# SCHEMATIC_e_BOOK_READER__VERSIUNE_10_v26.net
KiCad netlist of a schematic drawn in EAGLE
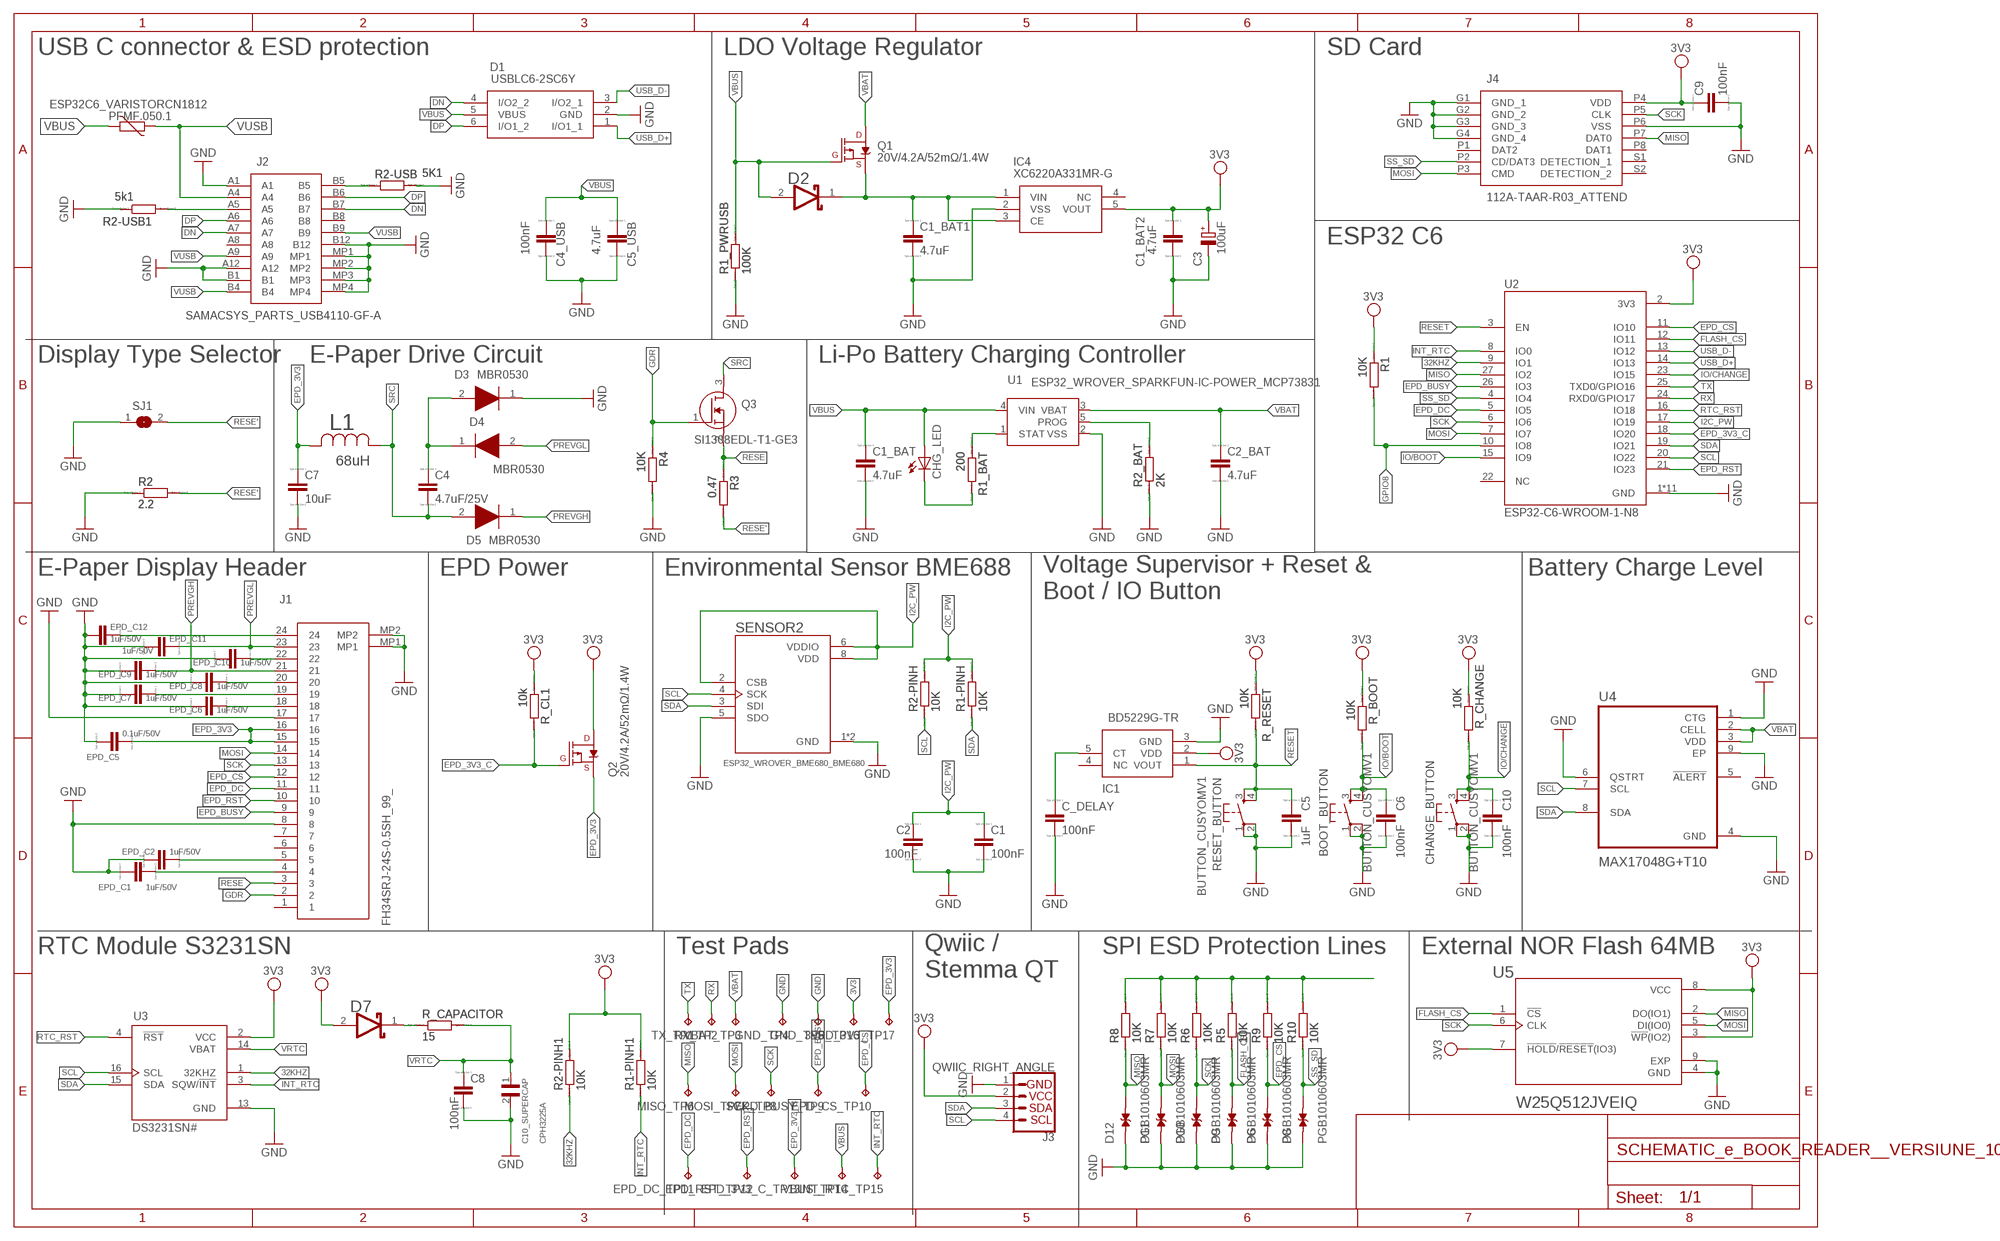
[diagram p0: schematic, sheet 1]

(export (version "E")
  (design (tool "Eeschema 10.0.6"))
  (components
    (comp (ref "3V3_TP16")
      (value "TPTP20R")
      (footprint "eagle-import:TP20R")
      (libsource (lib "eagle-import") (part "TPTP20R"))
    )
    (comp (ref "BOOT_BUTTON")
      (value "BUTTON_CUSYOMV1")
      (footprint "eagle-import:MYBUTTON")
      (libsource (lib "eagle-import") (part "BUTTON_CUSYOMV1"))
    )
    (comp (ref "C1")
      (value "100nF")
      (footprint "eagle-import:ESP32_WROVER_EAGLE-LTSPICE_C0402")
      (libsource (lib "eagle-import") (part "ESP32_WROVER_EAGLE-LTSPICE_CC0402"))
    )
    (comp (ref "C1_BAT")
      (value "4.7uF")
      (footprint "eagle-import:ESP32_WROVER_EAGLE-LTSPICE_C0402")
      (libsource (lib "eagle-import") (part "ESP32_WROVER_EAGLE-LTSPICE_CC0402"))
    )
    (comp (ref "C1_BAT1")
      (value "4.7uF")
      (footprint "eagle-import:ESP32_WROVER_EAGLE-LTSPICE_C0402")
      (libsource (lib "eagle-import") (part "ESP32_WROVER_EAGLE-LTSPICE_CC0402"))
    )
    (comp (ref "C1_BAT2")
      (value "4.7uF")
      (footprint "eagle-import:ESP32_WROVER_EAGLE-LTSPICE_C0402")
      (libsource (lib "eagle-import") (part "ESP32_WROVER_EAGLE-LTSPICE_CC0402"))
    )
    (comp (ref "C2")
      (value "100nF")
      (footprint "eagle-import:ESP32_WROVER_EAGLE-LTSPICE_C0402")
      (libsource (lib "eagle-import") (part "ESP32_WROVER_EAGLE-LTSPICE_CC0402"))
    )
    (comp (ref "C2_BAT")
      (value "4.7uF")
      (footprint "eagle-import:ESP32_WROVER_EAGLE-LTSPICE_C0402")
      (libsource (lib "eagle-import") (part "ESP32_WROVER_EAGLE-LTSPICE_CC0402"))
    )
    (comp (ref "C3")
      (value "100uF")
      (footprint "eagle-import:RCL_CT3528")
      (libsource (lib "eagle-import") (part "RCL_CPOL-EUCT3528"))
    )
    (comp (ref "C4")
      (value "4.7uF/25V")
      (footprint "eagle-import:ESP32_WROVER_EAGLE-LTSPICE_C0402")
      (libsource (lib "eagle-import") (part "ESP32_WROVER_EAGLE-LTSPICE_CC0402"))
    )
    (comp (ref "C4_USB")
      (value "100nF")
      (footprint "eagle-import:ESP32_WROVER_EAGLE-LTSPICE_C0402")
      (libsource (lib "eagle-import") (part "ESP32_WROVER_EAGLE-LTSPICE_CC0402"))
    )
    (comp (ref "C5")
      (value "1uF")
      (footprint "eagle-import:ESP32_WROVER_EAGLE-LTSPICE_C0402")
      (libsource (lib "eagle-import") (part "ESP32_WROVER_EAGLE-LTSPICE_CC0402"))
    )
    (comp (ref "C5_USB")
      (value "4.7uF")
      (footprint "eagle-import:ESP32_WROVER_EAGLE-LTSPICE_C0402")
      (libsource (lib "eagle-import") (part "ESP32_WROVER_EAGLE-LTSPICE_CC0402"))
    )
    (comp (ref "C6")
      (value "100nF")
      (footprint "eagle-import:ESP32_WROVER_EAGLE-LTSPICE_C0402")
      (libsource (lib "eagle-import") (part "ESP32_WROVER_EAGLE-LTSPICE_CC0402"))
    )
    (comp (ref "C7")
      (value "10uF")
      (footprint "eagle-import:ESP32_WROVER_EAGLE-LTSPICE_C0402")
      (libsource (lib "eagle-import") (part "ESP32_WROVER_EAGLE-LTSPICE_CC0402"))
    )
    (comp (ref "C8")
      (value "100nF")
      (footprint "eagle-import:ESP32_WROVER_EAGLE-LTSPICE_C0402")
      (libsource (lib "eagle-import") (part "ESP32_WROVER_EAGLE-LTSPICE_CC0402"))
    )
    (comp (ref "C9")
      (value "100nF")
      (footprint "eagle-import:ESP32_WROVER_EAGLE-LTSPICE_C0402")
      (libsource (lib "eagle-import") (part "ESP32_WROVER_EAGLE-LTSPICE_CC0402"))
    )
    (comp (ref "C10")
      (value "100nF")
      (footprint "eagle-import:ESP32_WROVER_EAGLE-LTSPICE_C0402")
      (libsource (lib "eagle-import") (part "ESP32_WROVER_EAGLE-LTSPICE_CC0402"))
    )
    (comp (ref "C10_SUPERCAP")
      (value "CPH3225A")
      (footprint "eagle-import:CAPCP3225X100N")
      (fields (field (name "MF") "Seiko Instruments"))
      (libsource (lib "eagle-import") (part "CPH3225A"))
    )
    (comp (ref "CHANGE_BUTTON")
      (value "BUTTON_CUSYOMV1")
      (footprint "eagle-import:MYBUTTON")
      (libsource (lib "eagle-import") (part "BUTTON_CUSYOMV1"))
    )
    (comp (ref "CHG_LED")
      (value "ADAFRUIT_LEDCHIP-LED0603")
      (footprint "eagle-import:ADAFRUIT_CHIP-LED0603")
      (libsource (lib "eagle-import") (part "ADAFRUIT_LEDCHIP-LED0603"))
    )
    (comp (ref "C_DELAY")
      (value "100nF")
      (footprint "eagle-import:ESP32_WROVER_EAGLE-LTSPICE_C0402")
      (libsource (lib "eagle-import") (part "ESP32_WROVER_EAGLE-LTSPICE_CC0402"))
    )
    (comp (ref "D1")
      (value "USBLC6-2SC6Y")
      (footprint "eagle-import:SOT95P280X145-6N")
      (fields (field (name "MF") "STMicroelectronics"))
      (libsource (lib "eagle-import") (part "USBLC6-2SC6Y"))
    )
    (comp (ref "D2")
      (value "ESP32_WROVER_AVX---SD0805S020S1R0_AVX_SD0805S020S1R0_0_0AVX_SD0805S020S1R0_0_0")
      (footprint "eagle-import:ESP32_WROVER_AVX---SD0805S020S1R0_AVX_SD0805S020S1R0_0")
      (fields
        (field (name "DIGIKEY_PART_NUMBER") "478-7800-1-ND")
        (field (name "MF") "AVX")
        (field (name "MOUSER_PART_NUMBER") "581-SD0805S020S1R0")
      )
      (libsource (lib "eagle-import") (part "ESP32_WROVER_AVX---SD0805S020S1R0_AVX_SD0805S020S1R0_0_0AVX_SD0805S020S1R0_0_0"))
    )
    (comp (ref "D3")
      (value "MBR0530")
      (footprint "eagle-import:ESP32_WROVER_AVX---SD0805S020S1R0_AVX_SD0805S020S1R0_0")
      (fields (field (name "MF") "ON Semiconductor"))
      (libsource (lib "eagle-import") (part "MBR0530"))
    )
    (comp (ref "D4")
      (value "MBR0530")
      (footprint "eagle-import:ESP32_WROVER_AVX---SD0805S020S1R0_AVX_SD0805S020S1R0_0")
      (fields (field (name "MF") "ON Semiconductor"))
      (libsource (lib "eagle-import") (part "MBR0530"))
    )
    (comp (ref "D5")
      (value "MBR0530")
      (footprint "eagle-import:ESP32_WROVER_AVX---SD0805S020S1R0_AVX_SD0805S020S1R0_0")
      (fields (field (name "MF") "ON Semiconductor"))
      (libsource (lib "eagle-import") (part "MBR0530"))
    )
    (comp (ref "D6")
      (value "PGB1010603MR")
      (footprint "eagle-import:DIOC1608X36N")
      (fields (field (name "MF") "Littelfuse Inc."))
      (libsource (lib "eagle-import") (part "PGB1010603MR"))
    )
    (comp (ref "D7")
      (value "ESP32_WROVER_AVX---SD0805S020S1R0_AVX_SD0805S020S1R0_0_0AVX_SD0805S020S1R0_0_0")
      (footprint "eagle-import:ESP32_WROVER_AVX---SD0805S020S1R0_AVX_SD0805S020S1R0_0")
      (fields
        (field (name "DIGIKEY_PART_NUMBER") "478-7800-1-ND")
        (field (name "MF") "AVX")
        (field (name "MOUSER_PART_NUMBER") "581-SD0805S020S1R0")
      )
      (libsource (lib "eagle-import") (part "ESP32_WROVER_AVX---SD0805S020S1R0_AVX_SD0805S020S1R0_0_0AVX_SD0805S020S1R0_0_0"))
    )
    (comp (ref "D8")
      (value "PGB1010603MR")
      (footprint "eagle-import:DIOC1608X36N")
      (fields (field (name "MF") "Littelfuse Inc."))
      (libsource (lib "eagle-import") (part "PGB1010603MR"))
    )
    (comp (ref "D9")
      (value "PGB1010603MR")
      (footprint "eagle-import:DIOC1608X36N")
      (fields (field (name "MF") "Littelfuse Inc."))
      (libsource (lib "eagle-import") (part "PGB1010603MR"))
    )
    (comp (ref "D10")
      (value "PGB1010603MR")
      (footprint "eagle-import:DIOC1608X36N")
      (fields (field (name "MF") "Littelfuse Inc."))
      (libsource (lib "eagle-import") (part "PGB1010603MR"))
    )
    (comp (ref "D11")
      (value "PGB1010603MR")
      (footprint "eagle-import:DIOC1608X36N")
      (fields (field (name "MF") "Littelfuse Inc."))
      (libsource (lib "eagle-import") (part "PGB1010603MR"))
    )
    (comp (ref "D12")
      (value "PGB1010603MR")
      (footprint "eagle-import:DIOC1608X36N")
      (fields (field (name "MF") "Littelfuse Inc."))
      (libsource (lib "eagle-import") (part "PGB1010603MR"))
    )
    (comp (ref "EPD_3V3_C_TP13")
      (value "TPTP20R")
      (footprint "eagle-import:TP20R")
      (libsource (lib "eagle-import") (part "TPTP20R"))
    )
    (comp (ref "EPD_3V3_TP17")
      (value "TPTP20R")
      (footprint "eagle-import:TP20R")
      (libsource (lib "eagle-import") (part "TPTP20R"))
    )
    (comp (ref "EPD_BUSY_TP9")
      (value "TPTP20R")
      (footprint "eagle-import:TP20R")
      (libsource (lib "eagle-import") (part "TPTP20R"))
    )
    (comp (ref "EPD_C1")
      (value "1uF/50V")
      (footprint "eagle-import:ESP32_WROVER_EAGLE-LTSPICE_C0402")
      (libsource (lib "eagle-import") (part "ESP32_WROVER_EAGLE-LTSPICE_CC0402"))
    )
    (comp (ref "EPD_C2")
      (value "1uF/50V")
      (footprint "eagle-import:ESP32_WROVER_EAGLE-LTSPICE_C0402")
      (libsource (lib "eagle-import") (part "ESP32_WROVER_EAGLE-LTSPICE_CC0402"))
    )
    (comp (ref "EPD_C5")
      (value "0.1uF/50V")
      (footprint "eagle-import:ESP32_WROVER_EAGLE-LTSPICE_C0402")
      (libsource (lib "eagle-import") (part "ESP32_WROVER_EAGLE-LTSPICE_CC0402"))
    )
    (comp (ref "EPD_C6")
      (value "1uF/50V")
      (footprint "eagle-import:ESP32_WROVER_EAGLE-LTSPICE_C0402")
      (libsource (lib "eagle-import") (part "ESP32_WROVER_EAGLE-LTSPICE_CC0402"))
    )
    (comp (ref "EPD_C7")
      (value "1uF/50V")
      (footprint "eagle-import:ESP32_WROVER_EAGLE-LTSPICE_C0402")
      (libsource (lib "eagle-import") (part "ESP32_WROVER_EAGLE-LTSPICE_CC0402"))
    )
    (comp (ref "EPD_C8")
      (value "1uF/50V")
      (footprint "eagle-import:ESP32_WROVER_EAGLE-LTSPICE_C0402")
      (libsource (lib "eagle-import") (part "ESP32_WROVER_EAGLE-LTSPICE_CC0402"))
    )
    (comp (ref "EPD_C9")
      (value "1uF/50V")
      (footprint "eagle-import:ESP32_WROVER_EAGLE-LTSPICE_C0402")
      (libsource (lib "eagle-import") (part "ESP32_WROVER_EAGLE-LTSPICE_CC0402"))
    )
    (comp (ref "EPD_C10")
      (value "1uF/50V")
      (footprint "eagle-import:ESP32_WROVER_EAGLE-LTSPICE_C0402")
      (libsource (lib "eagle-import") (part "ESP32_WROVER_EAGLE-LTSPICE_CC0402"))
    )
    (comp (ref "EPD_C11")
      (value "1uF/50V")
      (footprint "eagle-import:ESP32_WROVER_EAGLE-LTSPICE_C0402")
      (libsource (lib "eagle-import") (part "ESP32_WROVER_EAGLE-LTSPICE_CC0402"))
    )
    (comp (ref "EPD_C12")
      (value "1uF/50V")
      (footprint "eagle-import:ESP32_WROVER_EAGLE-LTSPICE_C0402")
      (libsource (lib "eagle-import") (part "ESP32_WROVER_EAGLE-LTSPICE_CC0402"))
    )
    (comp (ref "EPD_CS_TP10")
      (value "TPTP20R")
      (footprint "eagle-import:TP20R")
      (libsource (lib "eagle-import") (part "TPTP20R"))
    )
    (comp (ref "EPD_DC_TP11")
      (value "TPTP20R")
      (footprint "eagle-import:TP20R")
      (libsource (lib "eagle-import") (part "TPTP20R"))
    )
    (comp (ref "EPD_RST_TP12")
      (value "TPTP20R")
      (footprint "eagle-import:TP20R")
      (libsource (lib "eagle-import") (part "TPTP20R"))
    )
    (comp (ref "GND_TP4")
      (value "TPTP20R")
      (footprint "eagle-import:TP20R")
      (libsource (lib "eagle-import") (part "TPTP20R"))
    )
    (comp (ref "GND_TP5")
      (value "TPTP20R")
      (footprint "eagle-import:TP20R")
      (libsource (lib "eagle-import") (part "TPTP20R"))
    )
    (comp (ref "IC1")
      (value "BD5229G-TR")
      (footprint "eagle-import:SOT95P280X125-5N")
      (fields (field (name "MOUSER_PART_NUMBER") "755-BD5229G-TR"))
      (libsource (lib "eagle-import") (part "BD5229G-TR"))
    )
    (comp (ref "IC4")
      (value "XC6220A331MR-G")
      (footprint "eagle-import:SOT95P280X120-5N")
      (fields (field (name "MOUSER_PART_NUMBER") "865-XC6220A331MR-G"))
      (libsource (lib "eagle-import") (part "XC6220A331MR-G"))
    )
    (comp (ref "INT_RTC_TP15")
      (value "TPTP20R")
      (footprint "eagle-import:TP20R")
      (libsource (lib "eagle-import") (part "TPTP20R"))
    )
    (comp (ref "J1")
      (value "FH34SRJ-24S-0.5SH_99_")
      (footprint "eagle-import:FH34SRJ24S05SH99")
      (fields
        (field (name "MANUFACTURER_PART_NUMBER") "FH34SRJ-24S-0.5SH(99)")
        (field (name "MOUSER_PART_NUMBER") "798-FH34SRJ24S05SH99")
      )
      (libsource (lib "eagle-import") (part "FH34SRJ-24S-0.5SH_99_"))
    )
    (comp (ref "J2")
      (value "SAMACSYS_PARTS_USB4110-GF-A")
      (footprint "eagle-import:SAMACSYS_PARTS_USB4110GFA")
      (fields
        (field (name "MANUFACTURER_PART_NUMBER") "USB4110-GF-A")
        (field (name "MOUSER_PART_NUMBER") "640-USB4110-GF-A")
      )
      (libsource (lib "eagle-import") (part "SAMACSYS_PARTS_USB4110-GF-A"))
    )
    (comp (ref "J3")
      (value "QWIIC_RIGHT_ANGLE")
      (footprint "eagle-import:JST04_1MM_RA")
      (libsource (lib "eagle-import") (part "QWIIC_CONNECTORJS-1MM"))
    )
    (comp (ref "J4")
      (value "112A-TAAR-R03_ATTEND")
      (footprint "eagle-import:112ATAARR03ATTEND")
      (fields (field (name "MANUFACTURER_PART_NUMBER") "112A-TAAR-R03 ATTEND"))
      (libsource (lib "eagle-import") (part "112A-TAAR-R03_ATTEND"))
    )
    (comp (ref "L1")
      (value "68uH")
      (footprint "eagle-import:IND_4828-WE-TPC_WRE")
      (fields
        (field (name "MANUFACTURER_PART_NUMBER") "744043680")
        (field (name "COPYRIGHT") "Copyright (C) 2024 Ultra Librarian. All rights reserved.")
      )
      (libsource (lib "eagle-import") (part "744043680IND_4828-WE-TPC_WRE"))
    )
    (comp (ref "MISO_TP6")
      (value "TPTP20R")
      (footprint "eagle-import:TP20R")
      (libsource (lib "eagle-import") (part "TPTP20R"))
    )
    (comp (ref "MOSI_TP7")
      (value "TPTP20R")
      (footprint "eagle-import:TP20R")
      (libsource (lib "eagle-import") (part "TPTP20R"))
    )
    (comp (ref "PFMF.050.1")
      (value "ESP32C6_VARISTORCN1812")
      (footprint "eagle-import:ESP32C6_VARISTOR_CT_CN1812")
      (libsource (lib "eagle-import") (part "ESP32C6_VARISTORCN1812"))
    )
    (comp (ref "Q1")
      (value "20V/4.2A/52mΩ/1.4W")
      (footprint "eagle-import:ESP32_WROVER_SPARKFUN-DISCRETESEMI_SOT23-3")
      (libsource (lib "eagle-import") (part "ESP32_WROVER_SPARKFUN-DISCRETESEMI_MOSFET_PCH-DMG2305UX-7"))
    )
    (comp (ref "Q2")
      (value "20V/4.2A/52mΩ/1.4W")
      (footprint "eagle-import:ESP32_WROVER_SPARKFUN-DISCRETESEMI_SOT23-3")
      (libsource (lib "eagle-import") (part "ESP32_WROVER_SPARKFUN-DISCRETESEMI_MOSFET_PCH-DMG2305UX-7"))
    )
    (comp (ref "Q3")
      (value "SI1308EDL-T1-GE3")
      (footprint "eagle-import:SOT65P210X110-3N")
      (fields (field (name "MF") "Vishay Siliconix"))
      (libsource (lib "eagle-import") (part "SI1308EDL-T1-GE3"))
    )
    (comp (ref "R1")
      (value "10K")
      (footprint "eagle-import:ESP32_WROVER_EAGLE-LTSPICE_R0402")
      (libsource (lib "eagle-import") (part "ESP32_WROVER_EAGLE-LTSPICE_RR0402"))
    )
    (comp (ref "R1-PINH")
      (value "10K")
      (footprint "eagle-import:ESP32_WROVER_EAGLE-LTSPICE_R0402")
      (libsource (lib "eagle-import") (part "ESP32_WROVER_EAGLE-LTSPICE_RR0402"))
    )
    (comp (ref "R1-PINH1")
      (value "10K")
      (footprint "eagle-import:ESP32_WROVER_EAGLE-LTSPICE_R0402")
      (libsource (lib "eagle-import") (part "ESP32_WROVER_EAGLE-LTSPICE_RR0402"))
    )
    (comp (ref "R1_BAT")
      (value "200")
      (footprint "eagle-import:ESP32_WROVER_EAGLE-LTSPICE_R0402")
      (libsource (lib "eagle-import") (part "ESP32_WROVER_EAGLE-LTSPICE_RR0402"))
    )
    (comp (ref "R1_PWRUSB")
      (value "100K")
      (footprint "eagle-import:ESP32_WROVER_EAGLE-LTSPICE_R0402")
      (libsource (lib "eagle-import") (part "ESP32_WROVER_EAGLE-LTSPICE_RR0402"))
    )
    (comp (ref "R2")
      (value "2.2")
      (footprint "eagle-import:ESP32_WROVER_EAGLE-LTSPICE_R0402")
      (libsource (lib "eagle-import") (part "ESP32_WROVER_EAGLE-LTSPICE_RR0402"))
    )
    (comp (ref "R2-PINH")
      (value "10K")
      (footprint "eagle-import:ESP32_WROVER_EAGLE-LTSPICE_R0402")
      (libsource (lib "eagle-import") (part "ESP32_WROVER_EAGLE-LTSPICE_RR0402"))
    )
    (comp (ref "R2-PINH1")
      (value "10K")
      (footprint "eagle-import:ESP32_WROVER_EAGLE-LTSPICE_R0402")
      (libsource (lib "eagle-import") (part "ESP32_WROVER_EAGLE-LTSPICE_RR0402"))
    )
    (comp (ref "R2-USB")
      (value "5K1")
      (footprint "eagle-import:ESP32_WROVER_EAGLE-LTSPICE_R0402")
      (libsource (lib "eagle-import") (part "ESP32_WROVER_EAGLE-LTSPICE_RR0402"))
    )
    (comp (ref "R2-USB1")
      (value "5k1")
      (footprint "eagle-import:ESP32_WROVER_EAGLE-LTSPICE_R0402")
      (libsource (lib "eagle-import") (part "ESP32_WROVER_EAGLE-LTSPICE_RR0402"))
    )
    (comp (ref "R2_BAT")
      (value "2K")
      (footprint "eagle-import:ESP32_WROVER_EAGLE-LTSPICE_R0402")
      (libsource (lib "eagle-import") (part "ESP32_WROVER_EAGLE-LTSPICE_RR0402"))
    )
    (comp (ref "R3")
      (value "0.47")
      (footprint "eagle-import:ESP32_WROVER_EAGLE-LTSPICE_R0402")
      (libsource (lib "eagle-import") (part "ESP32_WROVER_EAGLE-LTSPICE_RR0402"))
    )
    (comp (ref "R4")
      (value "10K")
      (footprint "eagle-import:ESP32_WROVER_EAGLE-LTSPICE_R0402")
      (libsource (lib "eagle-import") (part "ESP32_WROVER_EAGLE-LTSPICE_RR0402"))
    )
    (comp (ref "R5")
      (value "10K")
      (footprint "eagle-import:ESP32_WROVER_EAGLE-LTSPICE_R0402")
      (libsource (lib "eagle-import") (part "ESP32_WROVER_EAGLE-LTSPICE_RR0402"))
    )
    (comp (ref "R6")
      (value "10K")
      (footprint "eagle-import:ESP32_WROVER_EAGLE-LTSPICE_R0402")
      (libsource (lib "eagle-import") (part "ESP32_WROVER_EAGLE-LTSPICE_RR0402"))
    )
    (comp (ref "R7")
      (value "10K")
      (footprint "eagle-import:ESP32_WROVER_EAGLE-LTSPICE_R0402")
      (libsource (lib "eagle-import") (part "ESP32_WROVER_EAGLE-LTSPICE_RR0402"))
    )
    (comp (ref "R8")
      (value "10K")
      (footprint "eagle-import:ESP32_WROVER_EAGLE-LTSPICE_R0402")
      (libsource (lib "eagle-import") (part "ESP32_WROVER_EAGLE-LTSPICE_RR0402"))
    )
    (comp (ref "R9")
      (value "10K")
      (footprint "eagle-import:ESP32_WROVER_EAGLE-LTSPICE_R0402")
      (libsource (lib "eagle-import") (part "ESP32_WROVER_EAGLE-LTSPICE_RR0402"))
    )
    (comp (ref "R10")
      (value "10K")
      (footprint "eagle-import:ESP32_WROVER_EAGLE-LTSPICE_R0402")
      (libsource (lib "eagle-import") (part "ESP32_WROVER_EAGLE-LTSPICE_RR0402"))
    )
    (comp (ref "RESET_BUTTON")
      (value "BUTTON_CUSYOMV1")
      (footprint "eagle-import:MYBUTTON")
      (libsource (lib "eagle-import") (part "BUTTON_CUSYOMV1"))
    )
    (comp (ref "RX_TP2")
      (value "TPTP20R")
      (footprint "eagle-import:TP20R")
      (libsource (lib "eagle-import") (part "TPTP20R"))
    )
    (comp (ref "R_BOOT")
      (value "10K")
      (footprint "eagle-import:ESP32_WROVER_EAGLE-LTSPICE_R0402")
      (libsource (lib "eagle-import") (part "ESP32_WROVER_EAGLE-LTSPICE_RR0402"))
    )
    (comp (ref "R_CAPACITOR")
      (value "15")
      (footprint "eagle-import:ESP32_WROVER_EAGLE-LTSPICE_R0402")
      (libsource (lib "eagle-import") (part "ESP32_WROVER_EAGLE-LTSPICE_RR0402"))
    )
    (comp (ref "R_CHANGE")
      (value "10K")
      (footprint "eagle-import:ESP32_WROVER_EAGLE-LTSPICE_R0402")
      (libsource (lib "eagle-import") (part "ESP32_WROVER_EAGLE-LTSPICE_RR0402"))
    )
    (comp (ref "R_CL1")
      (value "10k")
      (footprint "eagle-import:ESP32_WROVER_EAGLE-LTSPICE_R0402")
      (libsource (lib "eagle-import") (part "ESP32_WROVER_EAGLE-LTSPICE_RR0402"))
    )
    (comp (ref "R_RESET")
      (value "10K")
      (footprint "eagle-import:ESP32_WROVER_EAGLE-LTSPICE_R0402")
      (libsource (lib "eagle-import") (part "ESP32_WROVER_EAGLE-LTSPICE_RR0402"))
    )
    (comp (ref "SCK_TP8")
      (value "TPTP20R")
      (footprint "eagle-import:TP20R")
      (libsource (lib "eagle-import") (part "TPTP20R"))
    )
    (comp (ref "SENSOR2")
      (value "ESP32_WROVER_BME680_BME680")
      (footprint "eagle-import:ESP32_WROVER_BME680_PSON80P300X300X100-8N")
      (fields (field (name "MF") "Bosch Sensortec") (field (name "MP") "BME680"))
      (libsource (lib "eagle-import") (part "ESP32_WROVER_BME680_BME680"))
    )
    (comp (ref "SJ1") (value "SJ") (footprint "eagle-import:SJ") (libsource (lib "eagle-import") (part "SJ")))
    (comp (ref "TX_TP1")
      (value "TPTP20R")
      (footprint "eagle-import:TP20R")
      (libsource (lib "eagle-import") (part "TPTP20R"))
    )
    (comp (ref "U1")
      (value "ESP32_WROVER_SPARKFUN-IC-POWER_MCP73831")
      (footprint "eagle-import:ESP32_WROVER_SPARKFUN-IC-POWER_SOT23-5")
      (libsource (lib "eagle-import") (part "ESP32_WROVER_SPARKFUN-IC-POWER_MCP73831"))
    )
    (comp (ref "U2")
      (value "ESP32-C6-WROOM-1-N8")
      (footprint "eagle-import:XCVR_ESP32-C6-WROOM-1-N8")
      (fields (field (name "MF") "Espressif Systems"))
      (libsource (lib "eagle-import") (part "ESP32-C6-WROOM-1-N8"))
    )
    (comp (ref "U3")
      (value "DS3231SN#")
      (footprint "eagle-import:SOIC127P1032X265-16N")
      (fields (field (name "MF") "Analog Devices"))
      (libsource (lib "eagle-import") (part "DS3231SN#"))
    )
    (comp (ref "U4")
      (value "MAX17048G+T10")
      (footprint "eagle-import:SON50P200X200X80-9N")
      (fields (field (name "MF") "Analog Devices"))
      (libsource (lib "eagle-import") (part "MAX17048G+T10"))
    )
    (comp (ref "U5")
      (value "W25Q512JVEIQ")
      (footprint "eagle-import:SON127P600X800X80-9N")
      (fields (field (name "MF") "Winbond Electronics"))
      (libsource (lib "eagle-import") (part "W25Q512JVEIQ"))
    )
    (comp (ref "VBAT_TP3")
      (value "TPTP20R")
      (footprint "eagle-import:TP20R")
      (libsource (lib "eagle-import") (part "TPTP20R"))
    )
    (comp (ref "VBUS_TP14")
      (value "TPTP20R")
      (footprint "eagle-import:TP20R")
      (libsource (lib "eagle-import") (part "TPTP20R"))
    )
  )
  (nets
    (net (code "1") (name "3V3") (class "Default")
      (node (ref "3V3_TP16") (pin "TP") (pinfunction "TP_TP") (pintype "input"))
      (node (ref "C1_BAT2") (pin "1") (pinfunction "1_1") (pintype "passive"))
      (node (ref "C3") (pin "+") (pinfunction "+_+") (pintype "passive"))
      (node (ref "C9") (pin "1") (pinfunction "1_1") (pintype "passive"))
      (node (ref "D7") (pin "2") (pinfunction "ANODE_2") (pintype "bidirectional"))
      (node (ref "IC1") (pin "2") (pinfunction "VDD_2") (pintype "bidirectional"))
      (node (ref "IC4") (pin "5") (pinfunction "VOUT_5") (pintype "bidirectional"))
      (node (ref "J3") (pin "2") (pinfunction "2_2") (pintype "power_in"))
      (node (ref "J4") (pin "P4") (pinfunction "VDD_P4") (pintype "bidirectional"))
      (node (ref "Q2") (pin "3") (pinfunction "D_3") (pintype "bidirectional"))
      (node (ref "R1") (pin "1") (pinfunction "1_1") (pintype "passive"))
      (node (ref "R1-PINH1") (pin "2") (pinfunction "2_2") (pintype "passive"))
      (node (ref "R2-PINH1") (pin "2") (pinfunction "2_2") (pintype "passive"))
      (node (ref "R_BOOT") (pin "1") (pinfunction "1_1") (pintype "passive"))
      (node (ref "R_CHANGE") (pin "1") (pinfunction "1_1") (pintype "passive"))
      (node (ref "R_CL1") (pin "1") (pinfunction "1_1") (pintype "passive"))
      (node (ref "R_RESET") (pin "1") (pinfunction "1_1") (pintype "passive"))
      (node (ref "U2") (pin "2") (pinfunction "3V3_2") (pintype "power_in"))
      (node (ref "U3") (pin "2") (pinfunction "VCC_2") (pintype "power_in"))
      (node (ref "U5") (pin "3") (pinfunction "~{WP}(IO2)_3") (pintype "bidirectional"))
      (node (ref "U5") (pin "7") (pinfunction "~{HOLD}/~{RESET}(IO3)_7") (pintype "bidirectional"))
      (node (ref "U5") (pin "8") (pinfunction "VCC_8") (pintype "power_in"))
    )
    (net (code "2") (name "32KHZ") (class "Default")
      (node (ref "R2-PINH1") (pin "1") (pinfunction "1_1") (pintype "passive"))
      (node (ref "U2") (pin "9") (pinfunction "IO1_9") (pintype "bidirectional"))
      (node (ref "U3") (pin "1") (pinfunction "32KHZ_1") (pintype "output"))
    )
    (net (code "3") (name "DN") (class "Default")
      (node (ref "D1") (pin "4") (pinfunction "I/O2_2_4") (pintype "bidirectional"))
      (node (ref "J2") (pin "A7") (pinfunction "A7_A7") (pintype "bidirectional"))
      (node (ref "J2") (pin "B7") (pinfunction "B7_B7") (pintype "bidirectional"))
    )
    (net (code "4") (name "DP") (class "Default")
      (node (ref "D1") (pin "6") (pinfunction "I/O1_2_6") (pintype "bidirectional"))
      (node (ref "J2") (pin "A6") (pinfunction "A6_A6") (pintype "bidirectional"))
      (node (ref "J2") (pin "B6") (pinfunction "B6_B6") (pintype "bidirectional"))
    )
    (net (code "5") (name "EPD_3V3") (class "Default")
      (node (ref "C7") (pin "1") (pinfunction "1_1") (pintype "passive"))
      (node (ref "EPD_3V3_TP17") (pin "TP") (pinfunction "TP_TP") (pintype "input"))
      (node (ref "EPD_C5") (pin "1") (pinfunction "1_1") (pintype "passive"))
      (node (ref "J1") (pin "15") (pinfunction "15_15") (pintype "bidirectional"))
      (node (ref "J1") (pin "16") (pinfunction "16_16") (pintype "bidirectional"))
      (node (ref "L1") (pin "2") (pinfunction "2_2") (pintype "passive"))
      (node (ref "Q2") (pin "2") (pinfunction "S_2") (pintype "bidirectional"))
    )
    (net (code "6") (name "EPD_3V3_C") (class "Default")
      (node (ref "EPD_3V3_C_TP13") (pin "TP") (pinfunction "TP_TP") (pintype "input"))
      (node (ref "Q2") (pin "1") (pinfunction "G_1") (pintype "bidirectional"))
      (node (ref "R_CL1") (pin "2") (pinfunction "2_2") (pintype "passive"))
      (node (ref "U2") (pin "18") (pinfunction "IO20_18") (pintype "bidirectional"))
    )
    (net (code "7") (name "EPD_BUSY") (class "Default")
      (node (ref "EPD_BUSY_TP9") (pin "TP") (pinfunction "TP_TP") (pintype "input"))
      (node (ref "J1") (pin "9") (pinfunction "9_9") (pintype "bidirectional"))
      (node (ref "U2") (pin "26") (pinfunction "IO3_26") (pintype "bidirectional"))
    )
    (net (code "8") (name "EPD_CS") (class "Default")
      (node (ref "D6") (pin "2") (pinfunction "2_2") (pintype "passive"))
      (node (ref "EPD_CS_TP10") (pin "TP") (pinfunction "TP_TP") (pintype "input"))
      (node (ref "J1") (pin "12") (pinfunction "12_12") (pintype "bidirectional"))
      (node (ref "R9") (pin "1") (pinfunction "1_1") (pintype "passive"))
      (node (ref "U2") (pin "11") (pinfunction "IO10_11") (pintype "bidirectional"))
    )
    (net (code "9") (name "EPD_DC") (class "Default")
      (node (ref "EPD_DC_TP11") (pin "TP") (pinfunction "TP_TP") (pintype "input"))
      (node (ref "J1") (pin "11") (pinfunction "11_11") (pintype "bidirectional"))
      (node (ref "U2") (pin "5") (pinfunction "IO5_5") (pintype "bidirectional"))
    )
    (net (code "10") (name "EPD_RST") (class "Default")
      (node (ref "EPD_RST_TP12") (pin "TP") (pinfunction "TP_TP") (pintype "input"))
      (node (ref "J1") (pin "10") (pinfunction "10_10") (pintype "bidirectional"))
      (node (ref "U2") (pin "21") (pinfunction "IO23_21") (pintype "bidirectional"))
    )
    (net (code "11") (name "FLASH_CS") (class "Default")
      (node (ref "D9") (pin "2") (pinfunction "2_2") (pintype "passive"))
      (node (ref "R5") (pin "1") (pinfunction "1_1") (pintype "passive"))
      (node (ref "U2") (pin "12") (pinfunction "IO11_12") (pintype "bidirectional"))
      (node (ref "U5") (pin "1") (pinfunction "~{CS}_1") (pintype "input"))
    )
    (net (code "12") (name "GDR") (class "Default")
      (node (ref "J1") (pin "2") (pinfunction "2_2") (pintype "bidirectional"))
      (node (ref "Q3") (pin "1") (pinfunction "G_1") (pintype "bidirectional"))
      (node (ref "R4") (pin "1") (pinfunction "1_1") (pintype "passive"))
    )
    (net (code "13") (name "GND") (class "Default")
      (node (ref "BOOT_BUTTON") (pin "1") (pinfunction "1_1") (pintype "passive"))
      (node (ref "BOOT_BUTTON") (pin "2") (pinfunction "2_2") (pintype "passive"))
      (node (ref "C1") (pin "2") (pinfunction "2_2") (pintype "passive"))
      (node (ref "C10") (pin "2") (pinfunction "2_2") (pintype "passive"))
      (node (ref "C10_SUPERCAP") (pin "2") (pinfunction "2_2") (pintype "passive"))
      (node (ref "C1_BAT") (pin "2") (pinfunction "2_2") (pintype "passive"))
      (node (ref "C1_BAT1") (pin "2") (pinfunction "2_2") (pintype "passive"))
      (node (ref "C1_BAT2") (pin "2") (pinfunction "2_2") (pintype "passive"))
      (node (ref "C2") (pin "2") (pinfunction "2_2") (pintype "passive"))
      (node (ref "C2_BAT") (pin "2") (pinfunction "2_2") (pintype "passive"))
      (node (ref "C3") (pin "-") (pinfunction "-_-") (pintype "passive"))
      (node (ref "C4_USB") (pin "2") (pinfunction "2_2") (pintype "passive"))
      (node (ref "C5") (pin "2") (pinfunction "2_2") (pintype "passive"))
      (node (ref "C5_USB") (pin "2") (pinfunction "2_2") (pintype "passive"))
      (node (ref "C6") (pin "2") (pinfunction "2_2") (pintype "passive"))
      (node (ref "C7") (pin "2") (pinfunction "2_2") (pintype "passive"))
      (node (ref "C8") (pin "2") (pinfunction "2_2") (pintype "passive"))
      (node (ref "C9") (pin "2") (pinfunction "2_2") (pintype "passive"))
      (node (ref "CHANGE_BUTTON") (pin "1") (pinfunction "1_1") (pintype "passive"))
      (node (ref "CHANGE_BUTTON") (pin "2") (pinfunction "2_2") (pintype "passive"))
      (node (ref "C_DELAY") (pin "2") (pinfunction "2_2") (pintype "passive"))
      (node (ref "D1") (pin "2") (pinfunction "GND_2") (pintype "bidirectional"))
      (node (ref "D10") (pin "1") (pinfunction "1_1") (pintype "passive"))
      (node (ref "D11") (pin "1") (pinfunction "1_1") (pintype "passive"))
      (node (ref "D12") (pin "1") (pinfunction "1_1") (pintype "passive"))
      (node (ref "D3") (pin "1") (pinfunction "K_1") (pintype "bidirectional"))
      (node (ref "D6") (pin "1") (pinfunction "1_1") (pintype "passive"))
      (node (ref "D8") (pin "1") (pinfunction "1_1") (pintype "passive"))
      (node (ref "D9") (pin "1") (pinfunction "1_1") (pintype "passive"))
      (node (ref "EPD_C1") (pin "2") (pinfunction "2_2") (pintype "passive"))
      (node (ref "EPD_C10") (pin "2") (pinfunction "2_2") (pintype "passive"))
      (node (ref "EPD_C11") (pin "2") (pinfunction "2_2") (pintype "passive"))
      (node (ref "EPD_C12") (pin "2") (pinfunction "2_2") (pintype "passive"))
      (node (ref "EPD_C2") (pin "2") (pinfunction "2_2") (pintype "passive"))
      (node (ref "EPD_C5") (pin "2") (pinfunction "2_2") (pintype "passive"))
      (node (ref "EPD_C6") (pin "2") (pinfunction "2_2") (pintype "passive"))
      (node (ref "EPD_C7") (pin "2") (pinfunction "2_2") (pintype "passive"))
      (node (ref "EPD_C8") (pin "2") (pinfunction "2_2") (pintype "passive"))
      (node (ref "EPD_C9") (pin "2") (pinfunction "2_2") (pintype "passive"))
      (node (ref "GND_TP4") (pin "TP") (pinfunction "TP_TP") (pintype "input"))
      (node (ref "GND_TP5") (pin "TP") (pinfunction "TP_TP") (pintype "input"))
      (node (ref "IC1") (pin "3") (pinfunction "GND_3") (pintype "bidirectional"))
      (node (ref "IC4") (pin "2") (pinfunction "VSS_2") (pintype "bidirectional"))
      (node (ref "J1") (pin "17") (pinfunction "17_17") (pintype "bidirectional"))
      (node (ref "J1") (pin "8") (pinfunction "8_8") (pintype "bidirectional"))
      (node (ref "J1") (pin "MP1") (pinfunction "MP1_MP1") (pintype "bidirectional"))
      (node (ref "J1") (pin "MP2") (pinfunction "MP2_MP2") (pintype "bidirectional"))
      (node (ref "J2") (pin "A1") (pinfunction "A1_A1") (pintype "bidirectional"))
      (node (ref "J2") (pin "A12") (pinfunction "A12_A12") (pintype "bidirectional"))
      (node (ref "J2") (pin "B1") (pinfunction "B1_B1") (pintype "bidirectional"))
      (node (ref "J2") (pin "B12") (pinfunction "B12_B12") (pintype "bidirectional"))
      (node (ref "J2") (pin "MP1") (pinfunction "MP1_MP1") (pintype "bidirectional"))
      (node (ref "J2") (pin "MP2") (pinfunction "MP2_MP2") (pintype "bidirectional"))
      (node (ref "J2") (pin "MP3") (pinfunction "MP3_MP3") (pintype "bidirectional"))
      (node (ref "J2") (pin "MP4") (pinfunction "MP4_MP4") (pintype "bidirectional"))
      (node (ref "J3") (pin "1") (pinfunction "1_1") (pintype "power_in"))
      (node (ref "J4") (pin "G1") (pinfunction "GND_1_G1") (pintype "bidirectional"))
      (node (ref "J4") (pin "G2") (pinfunction "GND_2_G2") (pintype "bidirectional"))
      (node (ref "J4") (pin "G3") (pinfunction "GND_3_G3") (pintype "bidirectional"))
      (node (ref "J4") (pin "G4") (pinfunction "GND_4_G4") (pintype "bidirectional"))
      (node (ref "J4") (pin "P6") (pinfunction "VSS_P6") (pintype "bidirectional"))
      (node (ref "R1_PWRUSB") (pin "1") (pinfunction "1_1") (pintype "passive"))
      (node (ref "R2") (pin "1") (pinfunction "1_1") (pintype "passive"))
      (node (ref "R2-USB") (pin "2") (pinfunction "2_2") (pintype "passive"))
      (node (ref "R2-USB1") (pin "1") (pinfunction "1_1") (pintype "passive"))
      (node (ref "R2_BAT") (pin "1") (pinfunction "1_1") (pintype "passive"))
      (node (ref "R4") (pin "2") (pinfunction "2_2") (pintype "passive"))
      (node (ref "RESET_BUTTON") (pin "1") (pinfunction "1_1") (pintype "passive"))
      (node (ref "RESET_BUTTON") (pin "2") (pinfunction "2_2") (pintype "passive"))
      (node (ref "SENSOR2") (pin "1") (pinfunction "GND_1") (pintype "power_in"))
      (node (ref "SENSOR2") (pin "5") (pinfunction "SDO_5") (pintype "bidirectional"))
      (node (ref "SENSOR2") (pin "7") (pinfunction "GND_7") (pintype "power_in"))
      (node (ref "SJ1") (pin "1") (pinfunction "1_1") (pintype "passive"))
      (node (ref "U1") (pin "2") (pinfunction "VSS_2") (pintype "power_in"))
      (node (ref "U2") (pin "1") (pinfunction "GND_1") (pintype "power_in"))
      (node (ref "U2") (pin "28") (pinfunction "GND_28") (pintype "power_in"))
      (node (ref "U2") (pin "29_1") (pinfunction "GND_29_1") (pintype "power_in"))
      (node (ref "U2") (pin "29_2") (pinfunction "GND_29_2") (pintype "power_in"))
      (node (ref "U2") (pin "29_3") (pinfunction "GND_29_3") (pintype "power_in"))
      (node (ref "U2") (pin "29_4") (pinfunction "GND_29_4") (pintype "power_in"))
      (node (ref "U2") (pin "29_5") (pinfunction "GND_29_5") (pintype "power_in"))
      (node (ref "U2") (pin "29_6") (pinfunction "GND_29_6") (pintype "power_in"))
      (node (ref "U2") (pin "29_7") (pinfunction "GND_29_7") (pintype "power_in"))
      (node (ref "U2") (pin "29_8") (pinfunction "GND_29_8") (pintype "power_in"))
      (node (ref "U2") (pin "29_9") (pinfunction "GND_29_9") (pintype "power_in"))
      (node (ref "U3") (pin "13") (pinfunction "GND_13") (pintype "power_in"))
      (node (ref "U4") (pin "1") (pinfunction "CTG_1") (pintype "power_in"))
      (node (ref "U4") (pin "4") (pinfunction "GND_4") (pintype "power_in"))
      (node (ref "U4") (pin "6") (pinfunction "QSTRT_6") (pintype "input"))
      (node (ref "U4") (pin "9") (pinfunction "EP_9") (pintype "power_in"))
      (node (ref "U5") (pin "4") (pinfunction "GND_4") (pintype "power_in"))
      (node (ref "U5") (pin "9") (pinfunction "EXP_9") (pintype "passive"))
    )
    (net (code "14") (name "GPIO8") (class "Default")
      (node (ref "R1") (pin "2") (pinfunction "2_2") (pintype "passive"))
      (node (ref "U2") (pin "10") (pinfunction "IO8_10") (pintype "bidirectional"))
    )
    (net (code "15") (name "I2C_PW") (class "Default")
      (node (ref "C1") (pin "1") (pinfunction "1_1") (pintype "passive"))
      (node (ref "C2") (pin "1") (pinfunction "1_1") (pintype "passive"))
      (node (ref "R1-PINH") (pin "2") (pinfunction "2_2") (pintype "passive"))
      (node (ref "R2-PINH") (pin "2") (pinfunction "2_2") (pintype "passive"))
      (node (ref "SENSOR2") (pin "2") (pinfunction "CSB_2") (pintype "input"))
      (node (ref "SENSOR2") (pin "6") (pinfunction "VDDIO_6") (pintype "power_in"))
      (node (ref "SENSOR2") (pin "8") (pinfunction "VDD_8") (pintype "power_in"))
      (node (ref "U2") (pin "17") (pinfunction "IO19_17") (pintype "bidirectional"))
    )
    (net (code "16") (name "INT_RTC") (class "Default")
      (node (ref "INT_RTC_TP15") (pin "TP") (pinfunction "TP_TP") (pintype "input"))
      (node (ref "R1-PINH1") (pin "1") (pinfunction "1_1") (pintype "passive"))
      (node (ref "U2") (pin "8") (pinfunction "IO0_8") (pintype "bidirectional"))
      (node (ref "U3") (pin "3") (pinfunction "SQW/~{INT}_3") (pintype "output"))
    )
    (net (code "17") (name "IO{slash}BOOT") (class "Default")
      (node (ref "BOOT_BUTTON") (pin "3") (pinfunction "3_3") (pintype "passive"))
      (node (ref "BOOT_BUTTON") (pin "4") (pinfunction "4_4") (pintype "passive"))
      (node (ref "C6") (pin "1") (pinfunction "1_1") (pintype "passive"))
      (node (ref "R_BOOT") (pin "2") (pinfunction "2_2") (pintype "passive"))
      (node (ref "U2") (pin "15") (pinfunction "IO9_15") (pintype "bidirectional"))
    )
    (net (code "18") (name "IO{slash}CHANGE") (class "Default")
      (node (ref "C10") (pin "1") (pinfunction "1_1") (pintype "passive"))
      (node (ref "CHANGE_BUTTON") (pin "3") (pinfunction "3_3") (pintype "passive"))
      (node (ref "CHANGE_BUTTON") (pin "4") (pinfunction "4_4") (pintype "passive"))
      (node (ref "R_CHANGE") (pin "2") (pinfunction "2_2") (pintype "passive"))
      (node (ref "U2") (pin "23") (pinfunction "IO15_23") (pintype "bidirectional"))
    )
    (net (code "19") (name "MISO") (class "Default")
      (node (ref "D12") (pin "2") (pinfunction "2_2") (pintype "passive"))
      (node (ref "J4") (pin "P7") (pinfunction "DAT0_P7") (pintype "bidirectional"))
      (node (ref "MISO_TP6") (pin "TP") (pinfunction "TP_TP") (pintype "input"))
      (node (ref "R8") (pin "1") (pinfunction "1_1") (pintype "passive"))
      (node (ref "U2") (pin "27") (pinfunction "IO2_27") (pintype "bidirectional"))
      (node (ref "U5") (pin "2") (pinfunction "DO(IO1)_2") (pintype "bidirectional"))
    )
    (net (code "20") (name "MOSI") (class "Default")
      (node (ref "D11") (pin "2") (pinfunction "2_2") (pintype "passive"))
      (node (ref "J1") (pin "14") (pinfunction "14_14") (pintype "bidirectional"))
      (node (ref "J4") (pin "P3") (pinfunction "CMD_P3") (pintype "bidirectional"))
      (node (ref "MOSI_TP7") (pin "TP") (pinfunction "TP_TP") (pintype "input"))
      (node (ref "R7") (pin "1") (pinfunction "1_1") (pintype "passive"))
      (node (ref "U2") (pin "7") (pinfunction "IO7_7") (pintype "bidirectional"))
      (node (ref "U5") (pin "5") (pinfunction "DI(IO0)_5") (pintype "bidirectional"))
    )
    (net (code "21") (name "Net-(CHG_LED-PadC)") (class "Default")
      (node (ref "CHG_LED") (pin "C") (pinfunction "C_C") (pintype "passive"))
      (node (ref "R1_BAT") (pin "2") (pinfunction "2_2") (pintype "passive"))
    )
    (net (code "22") (name "Net-(D2-CATHODE)") (class "Default")
      (node (ref "C1_BAT1") (pin "1") (pinfunction "1_1") (pintype "passive"))
      (node (ref "D2") (pin "1") (pinfunction "CATHODE_1") (pintype "bidirectional"))
      (node (ref "IC4") (pin "1") (pinfunction "VIN_1") (pintype "bidirectional"))
      (node (ref "IC4") (pin "3") (pinfunction "CE_3") (pintype "bidirectional"))
      (node (ref "Q1") (pin "2") (pinfunction "S_2") (pintype "bidirectional"))
    )
    (net (code "23") (name "Net-(D3-A)") (class "Default")
      (node (ref "C4") (pin "1") (pinfunction "1_1") (pintype "passive"))
      (node (ref "D3") (pin "2") (pinfunction "A_2") (pintype "bidirectional"))
      (node (ref "D4") (pin "1") (pinfunction "K_1") (pintype "bidirectional"))
    )
    (net (code "24") (name "Net-(D7-CATHODE)") (class "Default")
      (node (ref "D7") (pin "1") (pinfunction "CATHODE_1") (pintype "bidirectional"))
      (node (ref "R_CAPACITOR") (pin "1") (pinfunction "1_1") (pintype "passive"))
    )
    (net (code "25") (name "Net-(EPD_C1-Pad1)") (class "Default")
      (node (ref "EPD_C1") (pin "1") (pinfunction "1_1") (pintype "passive"))
      (node (ref "J1") (pin "4") (pinfunction "4_4") (pintype "bidirectional"))
    )
    (net (code "26") (name "Net-(EPD_C2-Pad1)") (class "Default")
      (node (ref "EPD_C2") (pin "1") (pinfunction "1_1") (pintype "passive"))
      (node (ref "J1") (pin "5") (pinfunction "5_5") (pintype "bidirectional"))
    )
    (net (code "27") (name "Net-(EPD_C6-Pad1)") (class "Default")
      (node (ref "EPD_C6") (pin "1") (pinfunction "1_1") (pintype "passive"))
      (node (ref "J1") (pin "18") (pinfunction "18_18") (pintype "bidirectional"))
    )
    (net (code "28") (name "Net-(EPD_C7-Pad1)") (class "Default")
      (node (ref "EPD_C7") (pin "1") (pinfunction "1_1") (pintype "passive"))
      (node (ref "J1") (pin "19") (pinfunction "19_19") (pintype "bidirectional"))
    )
    (net (code "29") (name "Net-(EPD_C8-Pad1)") (class "Default")
      (node (ref "EPD_C8") (pin "1") (pinfunction "1_1") (pintype "passive"))
      (node (ref "J1") (pin "20") (pinfunction "20_20") (pintype "bidirectional"))
    )
    (net (code "30") (name "Net-(EPD_C10-Pad1)") (class "Default")
      (node (ref "EPD_C10") (pin "1") (pinfunction "1_1") (pintype "passive"))
      (node (ref "J1") (pin "22") (pinfunction "22_22") (pintype "bidirectional"))
    )
    (net (code "31") (name "Net-(EPD_C12-Pad1)") (class "Default")
      (node (ref "EPD_C12") (pin "1") (pinfunction "1_1") (pintype "passive"))
      (node (ref "J1") (pin "24") (pinfunction "24_24") (pintype "bidirectional"))
    )
    (net (code "32") (name "Net-(IC1-CT)") (class "Default")
      (node (ref "C_DELAY") (pin "1") (pinfunction "1_1") (pintype "passive"))
      (node (ref "IC1") (pin "5") (pinfunction "CT_5") (pintype "bidirectional"))
    )
    (net (code "33") (name "Net-(J2-PadA5)") (class "Default")
      (node (ref "J2") (pin "A5") (pinfunction "A5_A5") (pintype "bidirectional"))
      (node (ref "R2-USB1") (pin "2") (pinfunction "2_2") (pintype "passive"))
    )
    (net (code "34") (name "Net-(J2-PadB5)") (class "Default")
      (node (ref "J2") (pin "B5") (pinfunction "B5_B5") (pintype "bidirectional"))
      (node (ref "R2-USB") (pin "1") (pinfunction "1_1") (pintype "passive"))
    )
    (net (code "35") (name "Net-(R10-Pad2)") (class "Default")
      (node (ref "R10") (pin "2") (pinfunction "2_2") (pintype "passive"))
      (node (ref "R5") (pin "2") (pinfunction "2_2") (pintype "passive"))
      (node (ref "R6") (pin "2") (pinfunction "2_2") (pintype "passive"))
      (node (ref "R7") (pin "2") (pinfunction "2_2") (pintype "passive"))
      (node (ref "R8") (pin "2") (pinfunction "2_2") (pintype "passive"))
      (node (ref "R9") (pin "2") (pinfunction "2_2") (pintype "passive"))
    )
    (net (code "36") (name "Net-(U1-PROG)") (class "Default")
      (node (ref "R2_BAT") (pin "2") (pinfunction "2_2") (pintype "passive"))
      (node (ref "U1") (pin "5") (pinfunction "PROG_5") (pintype "input"))
    )
    (net (code "37") (name "Net-(U1-STAT)") (class "Default")
      (node (ref "R1_BAT") (pin "1") (pinfunction "1_1") (pintype "passive"))
      (node (ref "U1") (pin "1") (pinfunction "STAT_1") (pintype "output"))
    )
    (net (code "38") (name "PREVGH") (class "Default")
      (node (ref "D5") (pin "1") (pinfunction "K_1") (pintype "bidirectional"))
      (node (ref "EPD_C9") (pin "1") (pinfunction "1_1") (pintype "passive"))
      (node (ref "J1") (pin "21") (pinfunction "21_21") (pintype "bidirectional"))
    )
    (net (code "39") (name "PREVGL") (class "Default")
      (node (ref "D4") (pin "2") (pinfunction "A_2") (pintype "bidirectional"))
      (node (ref "EPD_C11") (pin "1") (pinfunction "1_1") (pintype "passive"))
      (node (ref "J1") (pin "23") (pinfunction "23_23") (pintype "bidirectional"))
    )
    (net (code "40") (name "RESE") (class "Default")
      (node (ref "J1") (pin "3") (pinfunction "3_3") (pintype "bidirectional"))
      (node (ref "Q3") (pin "2") (pinfunction "S_2") (pintype "bidirectional"))
      (node (ref "R3") (pin "1") (pinfunction "1_1") (pintype "passive"))
    )
    (net (code "41") (name "RESE'") (class "Default")
      (node (ref "R2") (pin "2") (pinfunction "2_2") (pintype "passive"))
      (node (ref "R3") (pin "2") (pinfunction "2_2") (pintype "passive"))
      (node (ref "SJ1") (pin "2") (pinfunction "2_2") (pintype "passive"))
    )
    (net (code "42") (name "RESET") (class "Default")
      (node (ref "C5") (pin "1") (pinfunction "1_1") (pintype "passive"))
      (node (ref "IC1") (pin "1") (pinfunction "VOUT_1") (pintype "bidirectional"))
      (node (ref "RESET_BUTTON") (pin "3") (pinfunction "3_3") (pintype "passive"))
      (node (ref "RESET_BUTTON") (pin "4") (pinfunction "4_4") (pintype "passive"))
      (node (ref "R_RESET") (pin "2") (pinfunction "2_2") (pintype "passive"))
      (node (ref "U2") (pin "3") (pinfunction "EN_3") (pintype "input"))
    )
    (net (code "43") (name "RTC_RST") (class "Default")
      (node (ref "U2") (pin "16") (pinfunction "IO18_16") (pintype "bidirectional"))
      (node (ref "U3") (pin "4") (pinfunction "~{RST}_4") (pintype "input"))
    )
    (net (code "44") (name "RX") (class "Default")
      (node (ref "RX_TP2") (pin "TP") (pinfunction "TP_TP") (pintype "input"))
      (node (ref "U2") (pin "24") (pinfunction "RXD0/GPIO17_24") (pintype "bidirectional"))
    )
    (net (code "45") (name "SCK") (class "Default")
      (node (ref "D10") (pin "2") (pinfunction "2_2") (pintype "passive"))
      (node (ref "J1") (pin "13") (pinfunction "13_13") (pintype "bidirectional"))
      (node (ref "J4") (pin "P5") (pinfunction "CLK_P5") (pintype "bidirectional"))
      (node (ref "R6") (pin "1") (pinfunction "1_1") (pintype "passive"))
      (node (ref "SCK_TP8") (pin "TP") (pinfunction "TP_TP") (pintype "input"))
      (node (ref "U2") (pin "6") (pinfunction "IO6_6") (pintype "bidirectional"))
      (node (ref "U5") (pin "6") (pinfunction "CLK_6") (pintype "input"))
    )
    (net (code "46") (name "SCL") (class "Default")
      (node (ref "J3") (pin "4") (pinfunction "4_4") (pintype "passive"))
      (node (ref "R2-PINH") (pin "1") (pinfunction "1_1") (pintype "passive"))
      (node (ref "SENSOR2") (pin "4") (pinfunction "SCK_4") (pintype "input"))
      (node (ref "U2") (pin "20") (pinfunction "IO22_20") (pintype "bidirectional"))
      (node (ref "U3") (pin "16") (pinfunction "SCL_16") (pintype "input"))
      (node (ref "U4") (pin "7") (pinfunction "SCL_7") (pintype "input"))
    )
    (net (code "47") (name "SDA") (class "Default")
      (node (ref "J3") (pin "3") (pinfunction "3_3") (pintype "passive"))
      (node (ref "R1-PINH") (pin "1") (pinfunction "1_1") (pintype "passive"))
      (node (ref "SENSOR2") (pin "3") (pinfunction "SDI_3") (pintype "bidirectional"))
      (node (ref "U2") (pin "19") (pinfunction "IO21_19") (pintype "bidirectional"))
      (node (ref "U3") (pin "15") (pinfunction "SDA_15") (pintype "bidirectional"))
      (node (ref "U4") (pin "8") (pinfunction "SDA_8") (pintype "bidirectional"))
    )
    (net (code "48") (name "SRC") (class "Default")
      (node (ref "C4") (pin "2") (pinfunction "2_2") (pintype "passive"))
      (node (ref "D5") (pin "2") (pinfunction "A_2") (pintype "bidirectional"))
      (node (ref "L1") (pin "1") (pinfunction "1_1") (pintype "passive"))
      (node (ref "Q3") (pin "3") (pinfunction "D_3") (pintype "bidirectional"))
    )
    (net (code "49") (name "SS_SD") (class "Default")
      (node (ref "D8") (pin "2") (pinfunction "2_2") (pintype "passive"))
      (node (ref "J4") (pin "P2") (pinfunction "CD/DAT3_P2") (pintype "bidirectional"))
      (node (ref "R10") (pin "1") (pinfunction "1_1") (pintype "passive"))
      (node (ref "U2") (pin "4") (pinfunction "IO4_4") (pintype "bidirectional"))
    )
    (net (code "50") (name "TX") (class "Default")
      (node (ref "TX_TP1") (pin "TP") (pinfunction "TP_TP") (pintype "input"))
      (node (ref "U2") (pin "25") (pinfunction "TXD0/GPIO16_25") (pintype "bidirectional"))
    )
    (net (code "51") (name "USB_D+") (class "Default")
      (node (ref "D1") (pin "1") (pinfunction "I/O1_1_1") (pintype "bidirectional"))
      (node (ref "U2") (pin "14") (pinfunction "IO13_14") (pintype "bidirectional"))
    )
    (net (code "52") (name "USB_D-") (class "Default")
      (node (ref "D1") (pin "3") (pinfunction "I/O2_1_3") (pintype "bidirectional"))
      (node (ref "U2") (pin "13") (pinfunction "IO12_13") (pintype "bidirectional"))
    )
    (net (code "53") (name "VBAT") (class "Default")
      (node (ref "C2_BAT") (pin "1") (pinfunction "1_1") (pintype "passive"))
      (node (ref "Q1") (pin "3") (pinfunction "D_3") (pintype "bidirectional"))
      (node (ref "U1") (pin "3") (pinfunction "VBAT_3") (pintype "power_in"))
      (node (ref "U4") (pin "2") (pinfunction "CELL_2") (pintype "power_in"))
      (node (ref "U4") (pin "3") (pinfunction "VDD_3") (pintype "power_in"))
      (node (ref "VBAT_TP3") (pin "TP") (pinfunction "TP_TP") (pintype "input"))
    )
    (net (code "54") (name "VBUS") (class "Default")
      (node (ref "C1_BAT") (pin "1") (pinfunction "1_1") (pintype "passive"))
      (node (ref "C4_USB") (pin "1") (pinfunction "1_1") (pintype "passive"))
      (node (ref "C5_USB") (pin "1") (pinfunction "1_1") (pintype "passive"))
      (node (ref "CHG_LED") (pin "A") (pinfunction "A_A") (pintype "passive"))
      (node (ref "D1") (pin "5") (pinfunction "VBUS_5") (pintype "bidirectional"))
      (node (ref "D2") (pin "2") (pinfunction "ANODE_2") (pintype "bidirectional"))
      (node (ref "PFMF.050.1") (pin "2") (pinfunction "2_2") (pintype "passive"))
      (node (ref "Q1") (pin "1") (pinfunction "G_1") (pintype "bidirectional"))
      (node (ref "R1_PWRUSB") (pin "2") (pinfunction "2_2") (pintype "passive"))
      (node (ref "U1") (pin "4") (pinfunction "VIN_4") (pintype "power_in"))
      (node (ref "VBUS_TP14") (pin "TP") (pinfunction "TP_TP") (pintype "input"))
    )
    (net (code "55") (name "VRTC") (class "Default")
      (node (ref "C10_SUPERCAP") (pin "1") (pinfunction "1_1") (pintype "passive"))
      (node (ref "C8") (pin "1") (pinfunction "1_1") (pintype "passive"))
      (node (ref "R_CAPACITOR") (pin "2") (pinfunction "2_2") (pintype "passive"))
      (node (ref "U3") (pin "14") (pinfunction "VBAT_14") (pintype "power_in"))
    )
    (net (code "56") (name "VUSB") (class "Default")
      (node (ref "J2") (pin "A4") (pinfunction "A4_A4") (pintype "bidirectional"))
      (node (ref "J2") (pin "A9") (pinfunction "A9_A9") (pintype "bidirectional"))
      (node (ref "J2") (pin "B4") (pinfunction "B4_B4") (pintype "bidirectional"))
      (node (ref "J2") (pin "B9") (pinfunction "B9_B9") (pintype "bidirectional"))
      (node (ref "PFMF.050.1") (pin "1") (pinfunction "1_1") (pintype "passive"))
    )
    (net (code "57") (name "unconnected-(IC1-NC-Pad4)") (class "Default")
      (node (ref "IC1") (pin "4") (pinfunction "NC_4") (pintype "no_connect"))
    )
    (net (code "58") (name "unconnected-(IC4-NC-Pad4)") (class "Default")
      (node (ref "IC4") (pin "4") (pinfunction "NC_4") (pintype "no_connect"))
    )
    (net (code "59") (name "unconnected-(J1-Pad1)") (class "Default")
      (node (ref "J1") (pin "1") (pinfunction "1_1") (pintype "bidirectional"))
    )
    (net (code "60") (name "unconnected-(J1-Pad6)") (class "Default")
      (node (ref "J1") (pin "6") (pinfunction "6_6") (pintype "bidirectional"))
    )
    (net (code "61") (name "unconnected-(J1-Pad7)") (class "Default")
      (node (ref "J1") (pin "7") (pinfunction "7_7") (pintype "bidirectional"))
    )
    (net (code "62") (name "unconnected-(J2-PadA8)") (class "Default")
      (node (ref "J2") (pin "A8") (pinfunction "A8_A8") (pintype "bidirectional"))
    )
    (net (code "63") (name "unconnected-(J2-PadB8)") (class "Default")
      (node (ref "J2") (pin "B8") (pinfunction "B8_B8") (pintype "bidirectional"))
    )
    (net (code "64") (name "unconnected-(J4-DAT1-PadP8)") (class "Default")
      (node (ref "J4") (pin "P8") (pinfunction "DAT1_P8") (pintype "bidirectional"))
    )
    (net (code "65") (name "unconnected-(J4-DAT2-PadP1)") (class "Default")
      (node (ref "J4") (pin "P1") (pinfunction "DAT2_P1") (pintype "bidirectional"))
    )
    (net (code "66") (name "unconnected-(J4-DETECTION_1-PadS1)") (class "Default")
      (node (ref "J4") (pin "S1") (pinfunction "DETECTION_1_S1") (pintype "bidirectional"))
    )
    (net (code "67") (name "unconnected-(J4-DETECTION_2-PadS2)") (class "Default")
      (node (ref "J4") (pin "S2") (pinfunction "DETECTION_2_S2") (pintype "bidirectional"))
    )
    (net (code "68") (name "unconnected-(U2-NC-Pad22)") (class "Default")
      (node (ref "U2") (pin "22") (pinfunction "NC_22") (pintype "no_connect"))
    )
    (net (code "69") (name "unconnected-(U4-~{ALERT}-Pad5)") (class "Default")
      (node (ref "U4") (pin "5") (pinfunction "~{ALERT}_5") (pintype "output"))
    )
  )
)
